# followEmSCH.net
KiCad netlist of a schematic drawn in Altium Designer
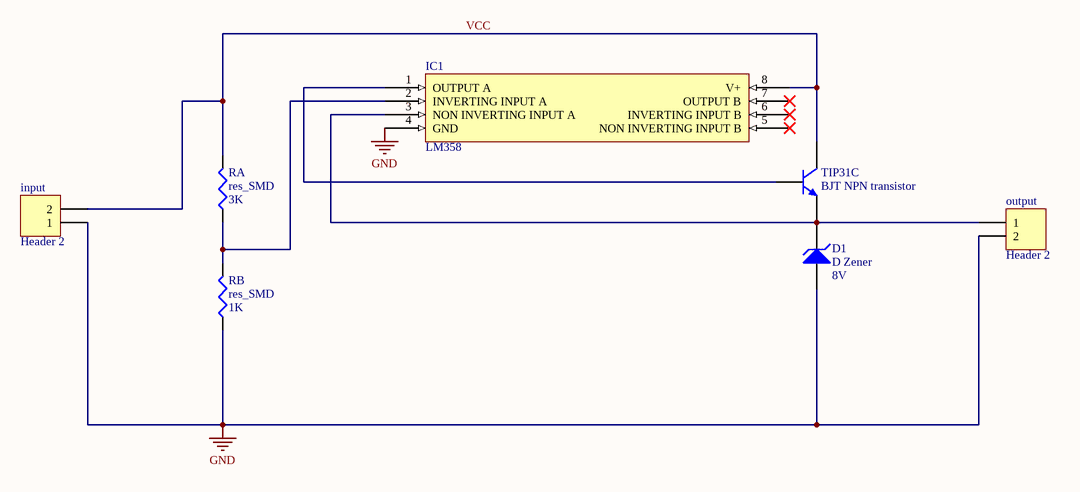
[diagram p0: followEmSCH.SchDoc]

(export (version "E")
  (design (tool "Eeschema 10.0.6"))
  (components
    (comp (ref "D1")
      (value "D Zener")
      (footprint "DO-214AC")
      (description "Zener Diode")
      (fields (field (name "ALTIUM_VALUE") "8V"))
      (libsource (lib "followEm") (part "D Zener"))
    )
    (comp (ref "IC1") (value "LM358") (footprint "SOIC-8") (libsource (lib "followEm") (part "LM358")))
    (comp (ref "input")
      (value "Header 2")
      (footprint "HDR1X2")
      (description "Header, 2-Pin")
      (fields (field (name "PUBLISHER") "Altium Limited"))
      (libsource (lib "") (part "Header 2_1"))
    )
    (comp (ref "output")
      (value "Header 2")
      (footprint "HDR1X2")
      (description "Header, 2-Pin")
      (fields (field (name "PUBLISHER") "Altium Limited"))
      (libsource (lib "Miscellaneous Connectors") (part "Header 2"))
    )
    (comp (ref "RA")
      (value "res_SMD")
      (footprint "RES 0805 2012")
      (description "Resistor")
      (fields (field (name "ALTIUM_VALUE") "3K") (field (name "PUBLISHER") "Altium Limited"))
      (libsource (lib "followEm") (part "res_SMD"))
    )
    (comp (ref "RB")
      (value "res_SMD")
      (footprint "RES 0805 2012")
      (description "Resistor")
      (fields (field (name "ALTIUM_VALUE") "1K") (field (name "PUBLISHER") "Altium Limited"))
      (libsource (lib "followEm") (part "res_SMD"))
    )
    (comp (ref "TIP31C")
      (value "BJT NPN transistor")
      (footprint "TO-220-AB")
      (description "NPN General Purpose Amplifier")
      (fields (field (name "PUBLISHER") "Altium Limited"))
      (libsource (lib "followEm") (part "BJT NPN transistor"))
    )
  )
  (nets
    (net (code "1") (name "/VCC") (class "Default")
      (node (ref "IC1") (pin "8") (pinfunction "V+_8") (pintype "input"))
      (node (ref "RA") (pin "2") (pinfunction "2_2") (pintype "passive"))
      (node (ref "TIP31C") (pin "2") (pinfunction "C_2") (pintype "passive"))
      (node (ref "input") (pin "2") (pinfunction "2_2") (pintype "passive"))
    )
    (net (code "2") (name "GND") (class "Default")
      (node (ref "D1") (pin "1") (pinfunction "A_1") (pintype "passive"))
      (node (ref "IC1") (pin "4") (pinfunction "GND_4") (pintype "input"))
      (node (ref "RB") (pin "1") (pinfunction "1_1") (pintype "passive"))
      (node (ref "input") (pin "1") (pinfunction "1_1") (pintype "passive"))
      (node (ref "output") (pin "2") (pinfunction "2_2") (pintype "passive"))
    )
    (net (code "3") (name "Net-(D1-K)") (class "Default")
      (node (ref "D1") (pin "2") (pinfunction "K_2") (pintype "passive"))
      (node (ref "IC1") (pin "3") (pinfunction "NON_INVERTING_INPUT_A_3") (pintype "input"))
      (node (ref "TIP31C") (pin "3") (pinfunction "E_3") (pintype "passive"))
      (node (ref "output") (pin "1") (pinfunction "1_1") (pintype "passive"))
    )
    (net (code "4") (name "Net-(IC1-INVERTING_INPUT_A)") (class "Default")
      (node (ref "IC1") (pin "2") (pinfunction "INVERTING_INPUT_A_2") (pintype "input"))
      (node (ref "RA") (pin "1") (pinfunction "1_1") (pintype "passive"))
      (node (ref "RB") (pin "2") (pinfunction "2_2") (pintype "passive"))
    )
    (net (code "5") (name "Net-(IC1-OUTPUT_A)") (class "Default")
      (node (ref "IC1") (pin "1") (pinfunction "OUTPUT_A_1") (pintype "input"))
      (node (ref "TIP31C") (pin "1") (pinfunction "B_1") (pintype "passive"))
    )
    (net (code "6") (name "unconnected-(IC1-INVERTING_INPUT_B-Pad6)") (class "Default")
      (node (ref "IC1") (pin "6") (pinfunction "INVERTING_INPUT_B_6") (pintype "input+no_connect"))
    )
    (net (code "7") (name "unconnected-(IC1-NON_INVERTING_INPUT_B-Pad5)") (class "Default")
      (node (ref "IC1") (pin "5") (pinfunction "NON_INVERTING_INPUT_B_5") (pintype "input+no_connect"))
    )
    (net (code "8") (name "unconnected-(IC1-OUTPUT_B-Pad7)") (class "Default")
      (node (ref "IC1") (pin "7") (pinfunction "OUTPUT_B_7") (pintype "input+no_connect"))
    )
  )
)
